# HYDRA_V2_1_NAV.net
KiCad netlist of a schematic drawn in Altium Designer
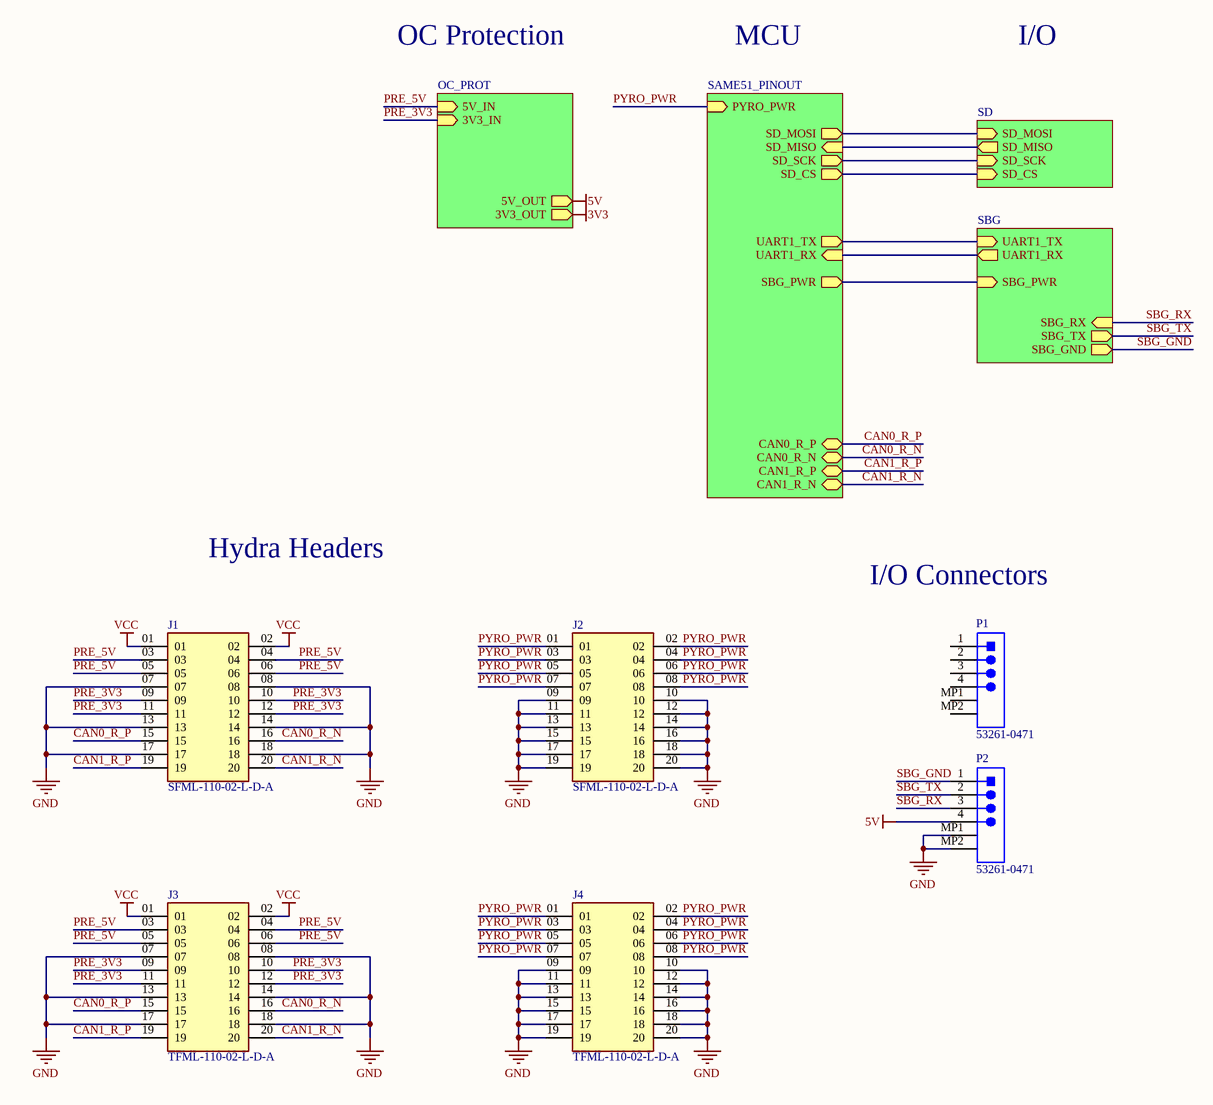
[diagram p0: HYDRA_V2.1_NAV.SchDoc]

(export (version "E")
  (design (tool "Eeschema 10.0.6"))
  (components
    (comp (ref "J1")
      (value "SFML-110-02-L-D-A")
      (footprint "SFML-110-02-L-D-A-Footprint-1")
      (description "Headers & Wire Housings .050 Tiger Eye High-Reliability Locking Socket Strip")
      (libsource (lib "uORocketry Hardware") (part "SFML-110-02-L-D-A"))
    )
    (comp (ref "J2")
      (value "SFML-110-02-L-D-A")
      (footprint "SFML-110-02-L-D-A-Footprint-1")
      (description "Headers & Wire Housings .050 Tiger Eye High-Reliability Locking Socket Strip")
      (libsource (lib "uORocketry Hardware") (part "SFML-110-02-L-D-A"))
    )
    (comp (ref "J3")
      (value "TFML-110-02-L-D-A")
      (footprint "TFML-110-02-L-D-A-Footprint-1")
      (description "Conn Shrouded Header (4 Sides) HDR 20 POS 1.27mm Solder ST Top Entry SMD TIGER EYE™ Tube")
      (libsource (lib "uORocketry Hardware") (part "TFML-110-02-L-D-A"))
    )
    (comp (ref "J4")
      (value "TFML-110-02-L-D-A")
      (footprint "TFML-110-02-L-D-A-Footprint-1")
      (description "Conn Shrouded Header (4 Sides) HDR 20 POS 1.27mm Solder ST Top Entry SMD TIGER EYE™ Tube")
      (libsource (lib "uORocketry Hardware") (part "TFML-110-02-L-D-A"))
    )
    (comp (ref "P1")
      (value "53261-0471")
      (footprint "MOLEX-53261-0471_V")
      (description "Male Header, Pitch 1.25 mm, 1 x 4 Position, Height 3.4 mm, -40 to 85 degC, RoHS, Tape and Reel")
      (fields (field (name "MANUFACTURER") "Molex"))
      (libsource (lib "Altium Content Vault") (part "CN-1P-2M-R4_A"))
    )
    (comp (ref "P2")
      (value "53261-0471")
      (footprint "MOLEX-53261-0471_V")
      (description "Male Header, Pitch 1.25 mm, 1 x 4 Position, Height 3.4 mm, -40 to 85 degC, RoHS, Tape and Reel")
      (fields (field (name "MANUFACTURER") "Molex"))
      (libsource (lib "Altium Content Vault") (part "CN-1P-2M-R4_A"))
    )
  )
  (nets
    (net (code "1") (name "/CAN0_R_N") (class "Default")
      (node (ref "J1") (pin "16") (pinfunction "16_16") (pintype "passive"))
      (node (ref "J3") (pin "16") (pinfunction "16_16") (pintype "passive"))
    )
    (net (code "2") (name "/CAN0_R_P") (class "Default")
      (node (ref "J1") (pin "15") (pinfunction "15_15") (pintype "passive"))
      (node (ref "J3") (pin "15") (pinfunction "15_15") (pintype "passive"))
    )
    (net (code "3") (name "/CAN1_R_N") (class "Default")
      (node (ref "J1") (pin "20") (pinfunction "20_20") (pintype "passive"))
      (node (ref "J3") (pin "20") (pinfunction "20_20") (pintype "passive"))
    )
    (net (code "4") (name "/CAN1_R_P") (class "Default")
      (node (ref "J1") (pin "19") (pinfunction "19_19") (pintype "passive"))
      (node (ref "J3") (pin "19") (pinfunction "19_19") (pintype "passive"))
    )
    (net (code "5") (name "/PRE_3V3") (class "Default")
      (node (ref "J1") (pin "09") (pinfunction "09_09") (pintype "passive"))
      (node (ref "J1") (pin "10") (pinfunction "10_10") (pintype "passive"))
      (node (ref "J1") (pin "11") (pinfunction "11_11") (pintype "passive"))
      (node (ref "J1") (pin "12") (pinfunction "12_12") (pintype "passive"))
      (node (ref "J3") (pin "09") (pinfunction "09_09") (pintype "passive"))
      (node (ref "J3") (pin "10") (pinfunction "10_10") (pintype "passive"))
      (node (ref "J3") (pin "11") (pinfunction "11_11") (pintype "passive"))
      (node (ref "J3") (pin "12") (pinfunction "12_12") (pintype "passive"))
    )
    (net (code "6") (name "/PRE_5V") (class "Default")
      (node (ref "J1") (pin "03") (pinfunction "03_03") (pintype "passive"))
      (node (ref "J1") (pin "04") (pinfunction "04_04") (pintype "passive"))
      (node (ref "J1") (pin "05") (pinfunction "05_05") (pintype "passive"))
      (node (ref "J1") (pin "06") (pinfunction "06_06") (pintype "passive"))
      (node (ref "J3") (pin "03") (pinfunction "03_03") (pintype "passive"))
      (node (ref "J3") (pin "04") (pinfunction "04_04") (pintype "passive"))
      (node (ref "J3") (pin "05") (pinfunction "05_05") (pintype "passive"))
      (node (ref "J3") (pin "06") (pinfunction "06_06") (pintype "passive"))
    )
    (net (code "7") (name "/PYRO_PWR") (class "Default")
      (node (ref "J2") (pin "01") (pinfunction "01_01") (pintype "passive"))
      (node (ref "J2") (pin "02") (pinfunction "02_02") (pintype "passive"))
      (node (ref "J2") (pin "03") (pinfunction "03_03") (pintype "passive"))
      (node (ref "J2") (pin "04") (pinfunction "04_04") (pintype "passive"))
      (node (ref "J2") (pin "05") (pinfunction "05_05") (pintype "passive"))
      (node (ref "J2") (pin "06") (pinfunction "06_06") (pintype "passive"))
      (node (ref "J2") (pin "07") (pinfunction "07_07") (pintype "passive"))
      (node (ref "J2") (pin "08") (pinfunction "08_08") (pintype "passive"))
      (node (ref "J4") (pin "01") (pinfunction "01_01") (pintype "passive"))
      (node (ref "J4") (pin "02") (pinfunction "02_02") (pintype "passive"))
      (node (ref "J4") (pin "03") (pinfunction "03_03") (pintype "passive"))
      (node (ref "J4") (pin "04") (pinfunction "04_04") (pintype "passive"))
      (node (ref "J4") (pin "05") (pinfunction "05_05") (pintype "passive"))
      (node (ref "J4") (pin "06") (pinfunction "06_06") (pintype "passive"))
      (node (ref "J4") (pin "07") (pinfunction "07_07") (pintype "passive"))
      (node (ref "J4") (pin "08") (pinfunction "08_08") (pintype "passive"))
    )
    (net (code "8") (name "/SBG_GND") (class "Default")
      (node (ref "P2") (pin "1") (pinfunction "1_1") (pintype "passive"))
    )
    (net (code "10") (name "/SBG_RX") (class "Default")
      (node (ref "P2") (pin "3") (pinfunction "3_3") (pintype "passive"))
    )
    (net (code "11") (name "/SBG_TX") (class "Default")
      (node (ref "P2") (pin "2") (pinfunction "2_2") (pintype "passive"))
    )
    (net (code "19") (name "5V") (class "Default")
      (node (ref "P2") (pin "4") (pinfunction "4_4") (pintype "passive"))
    )
    (net (code "20") (name "GND") (class "Default")
      (node (ref "J1") (pin "07") (pinfunction "07_07") (pintype "passive"))
      (node (ref "J1") (pin "08") (pinfunction "08_08") (pintype "passive"))
      (node (ref "J1") (pin "13") (pinfunction "13_13") (pintype "passive"))
      (node (ref "J1") (pin "14") (pinfunction "14_14") (pintype "passive"))
      (node (ref "J1") (pin "17") (pinfunction "17_17") (pintype "passive"))
      (node (ref "J1") (pin "18") (pinfunction "18_18") (pintype "passive"))
      (node (ref "J2") (pin "09") (pinfunction "09_09") (pintype "passive"))
      (node (ref "J2") (pin "10") (pinfunction "10_10") (pintype "passive"))
      (node (ref "J2") (pin "11") (pinfunction "11_11") (pintype "passive"))
      (node (ref "J2") (pin "12") (pinfunction "12_12") (pintype "passive"))
      (node (ref "J2") (pin "13") (pinfunction "13_13") (pintype "passive"))
      (node (ref "J2") (pin "14") (pinfunction "14_14") (pintype "passive"))
      (node (ref "J2") (pin "15") (pinfunction "15_15") (pintype "passive"))
      (node (ref "J2") (pin "16") (pinfunction "16_16") (pintype "passive"))
      (node (ref "J2") (pin "17") (pinfunction "17_17") (pintype "passive"))
      (node (ref "J2") (pin "18") (pinfunction "18_18") (pintype "passive"))
      (node (ref "J2") (pin "19") (pinfunction "19_19") (pintype "passive"))
      (node (ref "J2") (pin "20") (pinfunction "20_20") (pintype "passive"))
      (node (ref "J3") (pin "07") (pinfunction "07_07") (pintype "passive"))
      (node (ref "J3") (pin "08") (pinfunction "08_08") (pintype "passive"))
      (node (ref "J3") (pin "13") (pinfunction "13_13") (pintype "passive"))
      (node (ref "J3") (pin "14") (pinfunction "14_14") (pintype "passive"))
      (node (ref "J3") (pin "17") (pinfunction "17_17") (pintype "passive"))
      (node (ref "J3") (pin "18") (pinfunction "18_18") (pintype "passive"))
      (node (ref "J4") (pin "09") (pinfunction "09_09") (pintype "passive"))
      (node (ref "J4") (pin "10") (pinfunction "10_10") (pintype "passive"))
      (node (ref "J4") (pin "11") (pinfunction "11_11") (pintype "passive"))
      (node (ref "J4") (pin "12") (pinfunction "12_12") (pintype "passive"))
      (node (ref "J4") (pin "13") (pinfunction "13_13") (pintype "passive"))
      (node (ref "J4") (pin "14") (pinfunction "14_14") (pintype "passive"))
      (node (ref "J4") (pin "15") (pinfunction "15_15") (pintype "passive"))
      (node (ref "J4") (pin "16") (pinfunction "16_16") (pintype "passive"))
      (node (ref "J4") (pin "17") (pinfunction "17_17") (pintype "passive"))
      (node (ref "J4") (pin "18") (pinfunction "18_18") (pintype "passive"))
      (node (ref "J4") (pin "19") (pinfunction "19_19") (pintype "passive"))
      (node (ref "J4") (pin "20") (pinfunction "20_20") (pintype "passive"))
      (node (ref "P2") (pin "MP1") (pinfunction "MP1_MP1") (pintype "passive"))
      (node (ref "P2") (pin "MP2") (pinfunction "MP2_MP2") (pintype "passive"))
    )
    (net (code "21") (name "VCC") (class "Default")
      (node (ref "J1") (pin "01") (pinfunction "01_01") (pintype "passive"))
      (node (ref "J1") (pin "02") (pinfunction "02_02") (pintype "passive"))
      (node (ref "J3") (pin "01") (pinfunction "01_01") (pintype "passive"))
      (node (ref "J3") (pin "02") (pinfunction "02_02") (pintype "passive"))
    )
    (net (code "22") (name "unconnected-(P1-Pad1)") (class "Default")
      (node (ref "P1") (pin "1") (pinfunction "1_1") (pintype "passive"))
    )
    (net (code "23") (name "unconnected-(P1-Pad2)") (class "Default")
      (node (ref "P1") (pin "2") (pinfunction "2_2") (pintype "passive"))
    )
    (net (code "24") (name "unconnected-(P1-Pad3)") (class "Default")
      (node (ref "P1") (pin "3") (pinfunction "3_3") (pintype "passive"))
    )
    (net (code "25") (name "unconnected-(P1-Pad4)") (class "Default")
      (node (ref "P1") (pin "4") (pinfunction "4_4") (pintype "passive"))
    )
    (net (code "26") (name "unconnected-(P1-PadMP1)") (class "Default")
      (node (ref "P1") (pin "MP1") (pinfunction "MP1_MP1") (pintype "passive"))
    )
    (net (code "27") (name "unconnected-(P1-PadMP2)") (class "Default")
      (node (ref "P1") (pin "MP2") (pinfunction "MP2_MP2") (pintype "passive"))
    )
  )
)
